# ST-Link-V2_1.net
KiCad netlist of a schematic drawn in Altium Designer
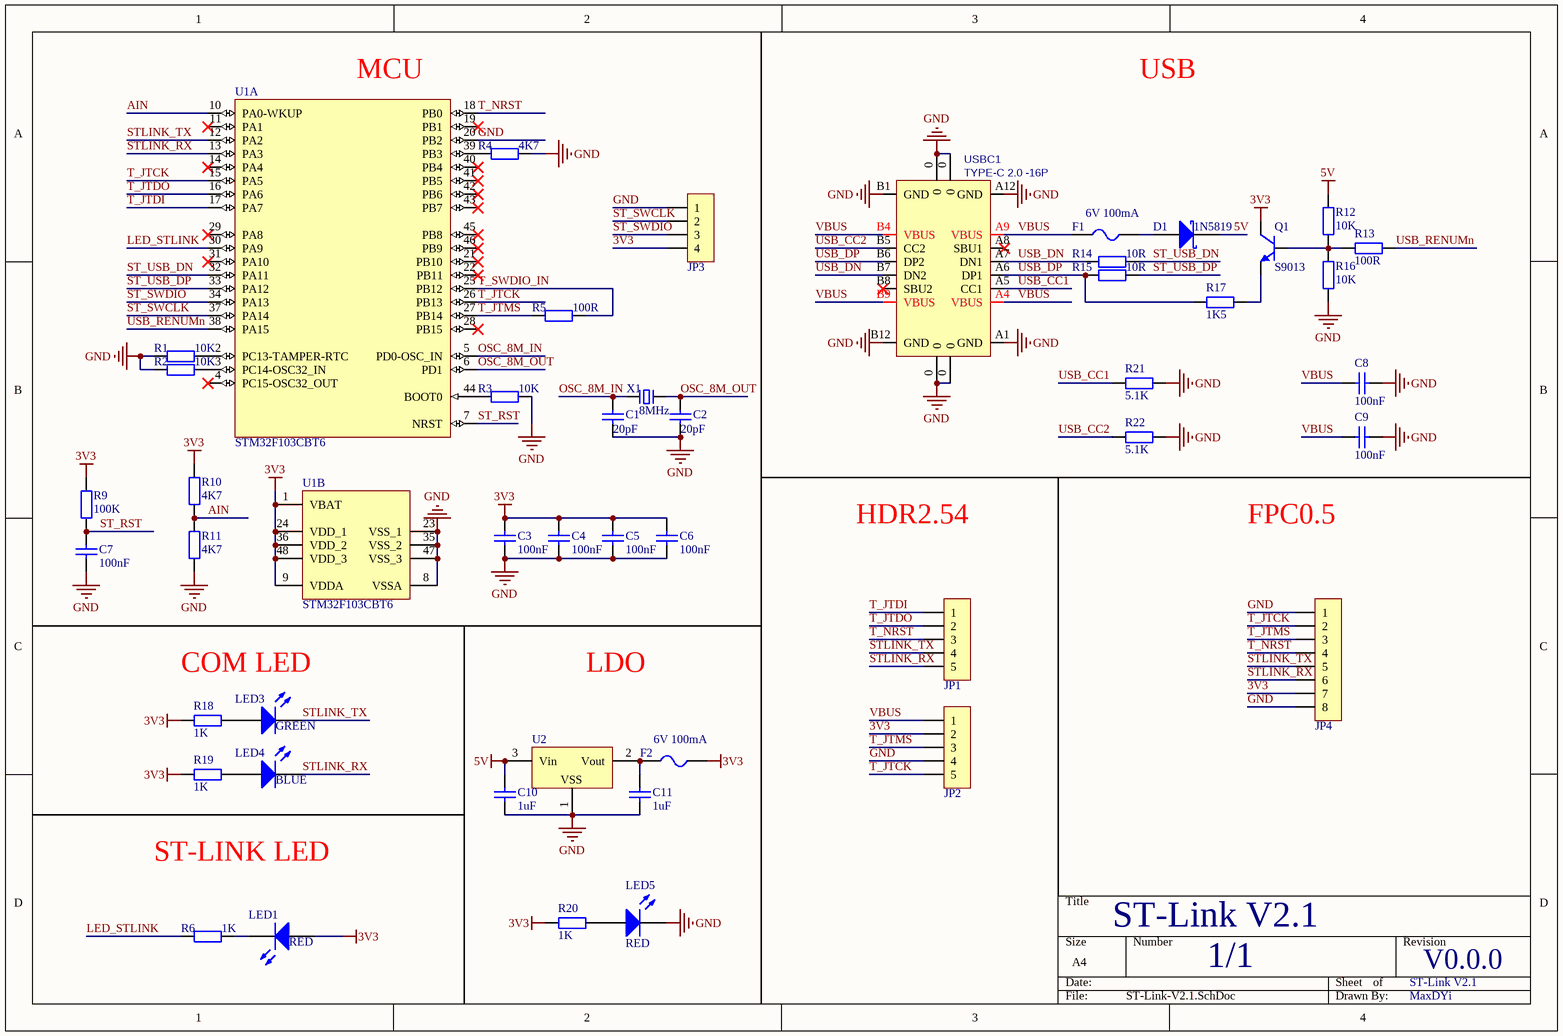
[diagram p0: ST-Link-V2.1.SchDoc]

(export (version "E")
  (design (tool "Eeschema 10.0.6"))
  (components
    (comp (ref "C1")
      (value "20pF")
      (footprint "C0402_M")
      (description "贴片电容/MLCC电容")
      (libsource (lib "0.1 - 电阻-电容-电感-保险丝-晶振-晶体-磁珠-电位器-法拉电容-馈通电容") (part "C"))
    )
    (comp (ref "C2")
      (value "20pF")
      (footprint "C0402_M")
      (description "贴片电容/MLCC电容")
      (libsource (lib "0.1 - 电阻-电容-电感-保险丝-晶振-晶体-磁珠-电位器-法拉电容-馈通电容") (part "C"))
    )
    (comp (ref "C3")
      (value "100nF")
      (footprint "C0402_M")
      (description "贴片电容/MLCC电容")
      (libsource (lib "0.1 - 电阻-电容-电感-保险丝-晶振-晶体-磁珠-电位器-法拉电容-馈通电容") (part "C"))
    )
    (comp (ref "C4")
      (value "100nF")
      (footprint "C0402_M")
      (description "贴片电容/MLCC电容")
      (libsource (lib "0.1 - 电阻-电容-电感-保险丝-晶振-晶体-磁珠-电位器-法拉电容-馈通电容") (part "C"))
    )
    (comp (ref "C5")
      (value "100nF")
      (footprint "C0402_M")
      (description "贴片电容/MLCC电容")
      (libsource (lib "0.1 - 电阻-电容-电感-保险丝-晶振-晶体-磁珠-电位器-法拉电容-馈通电容") (part "C"))
    )
    (comp (ref "C6")
      (value "100nF")
      (footprint "C0402_M")
      (description "贴片电容/MLCC电容")
      (libsource (lib "0.1 - 电阻-电容-电感-保险丝-晶振-晶体-磁珠-电位器-法拉电容-馈通电容") (part "C"))
    )
    (comp (ref "C7")
      (value "100nF")
      (footprint "C0402_M")
      (description "贴片电容/MLCC电容")
      (libsource (lib "0.1 - 电阻-电容-电感-保险丝-晶振-晶体-磁珠-电位器-法拉电容-馈通电容") (part "C"))
    )
    (comp (ref "C8")
      (value "100nF")
      (footprint "C0402_M")
      (description "贴片电容/MLCC电容")
      (libsource (lib "0.1 - 电阻-电容-电感-保险丝-晶振-晶体-磁珠-电位器-法拉电容-馈通电容") (part "C"))
    )
    (comp (ref "C9")
      (value "100nF")
      (footprint "C0402_M")
      (description "贴片电容/MLCC电容")
      (libsource (lib "0.1 - 电阻-电容-电感-保险丝-晶振-晶体-磁珠-电位器-法拉电容-馈通电容") (part "C"))
    )
    (comp (ref "C10")
      (value "1uF")
      (footprint "C0402_M")
      (description "贴片电容/MLCC电容")
      (libsource (lib "0.1 - 电阻-电容-电感-保险丝-晶振-晶体-磁珠-电位器-法拉电容-馈通电容") (part "C"))
    )
    (comp (ref "C11")
      (value "1uF")
      (footprint "C0402_M")
      (description "贴片电容/MLCC电容")
      (libsource (lib "0.1 - 电阻-电容-电感-保险丝-晶振-晶体-磁珠-电位器-法拉电容-馈通电容") (part "C"))
    )
    (comp (ref "D1")
      (value "1N5819")
      (footprint "SOD-323")
      (description "肖特基二极管")
      (libsource (lib "0.2 - 二极管-TVS-ESD-整流桥-放电管") (part "1N5819"))
    )
    (comp (ref "F1")
      (value "6V 100mA")
      (footprint "F0805")
      (description "方形保险丝")
      (libsource (lib "0.1 - 电阻-电容-电感-保险丝-晶振-晶体-磁珠-电位器-法拉电容-馈通电容") (part "FUSE-8.5*4.0*8.0"))
    )
    (comp (ref "F2")
      (value "6V 100mA")
      (footprint "F0805")
      (description "方形保险丝")
      (libsource (lib "0.1 - 电阻-电容-电感-保险丝-晶振-晶体-磁珠-电位器-法拉电容-馈通电容") (part "FUSE-8.5*4.0*8.0"))
    )
    (comp (ref "JP1")
      (value "HDR-1X5")
      (footprint "HDR2.54-WS-5P")
      (description "5P接插件")
      (libsource (lib "5.5 - 2.54mm连接器(KF2EDGK_XH2.54_2.54排针排母)") (part "Header 5"))
    )
    (comp (ref "JP2")
      (value "HDR-1X5")
      (footprint "HDR2.54-WS-5P")
      (description "5P接插件")
      (libsource (lib "5.5 - 2.54mm连接器(KF2EDGK_XH2.54_2.54排针排母)") (part "Header 5"))
    )
    (comp (ref "JP3")
      (value "HDR-1X4")
      (footprint "HDR1.27-LI-4P")
      (description "4P接插件")
      (libsource (lib "5.5 - 2.54mm连接器(KF2EDGK_XH2.54_2.54排针排母)") (part "Header 4"))
    )
    (comp (ref "JP4")
      (value "CON-8P")
      (footprint "FPC0.5-WT-8P-双侧触点")
      (description "8P连接器")
      (libsource (lib "4.9 - 0.5mm连接器(FPC0.5)") (part "Header 8"))
    )
    (comp (ref "LED1")
      (value "RED")
      (footprint "LED0603_R")
      (description "贴片LED")
      (libsource (lib "0.3 - LED发光二极管-IR二极管_接收管-光耦") (part "LED"))
    )
    (comp (ref "LED3")
      (value "GREEN")
      (footprint "LED0603_G")
      (description "贴片LED")
      (libsource (lib "0.3 - LED发光二极管-IR二极管_接收管-光耦") (part "LED"))
    )
    (comp (ref "LED4")
      (value "BLUE")
      (footprint "LED0603_B")
      (description "贴片LED")
      (libsource (lib "0.3 - LED发光二极管-IR二极管_接收管-光耦") (part "LED"))
    )
    (comp (ref "LED5")
      (value "RED")
      (footprint "LED0603_R")
      (description "贴片LED")
      (libsource (lib "0.3 - LED发光二极管-IR二极管_接收管-光耦") (part "LED"))
    )
    (comp (ref "Q1")
      (value "S9013")
      (footprint "SOT23-3N")
      (description "低频放大-NPN型")
      (libsource (lib "0.4 - 三极管-场效应管-可控硅") (part "9013-SMD"))
    )
    (comp (ref "R1")
      (value "10K")
      (footprint "R0402_M")
      (description "贴片电阻")
      (libsource (lib "0.1 - 电阻-电容-电感-保险丝-晶振-晶体-磁珠-电位器-法拉电容-馈通电容") (part "R"))
    )
    (comp (ref "R2")
      (value "10K")
      (footprint "R0402_M")
      (description "贴片电阻")
      (libsource (lib "0.1 - 电阻-电容-电感-保险丝-晶振-晶体-磁珠-电位器-法拉电容-馈通电容") (part "R"))
    )
    (comp (ref "R3")
      (value "10K")
      (footprint "R0402_M")
      (description "贴片电阻")
      (libsource (lib "0.1 - 电阻-电容-电感-保险丝-晶振-晶体-磁珠-电位器-法拉电容-馈通电容") (part "R"))
    )
    (comp (ref "R4")
      (value "4K7")
      (footprint "R0402_M")
      (description "贴片电阻")
      (libsource (lib "0.1 - 电阻-电容-电感-保险丝-晶振-晶体-磁珠-电位器-法拉电容-馈通电容") (part "R"))
    )
    (comp (ref "R5")
      (value "100R")
      (footprint "R0402_M")
      (description "贴片电阻")
      (libsource (lib "0.1 - 电阻-电容-电感-保险丝-晶振-晶体-磁珠-电位器-法拉电容-馈通电容") (part "R"))
    )
    (comp (ref "R6")
      (value "1K")
      (footprint "R0402_M")
      (description "贴片电阻")
      (libsource (lib "0.1 - 电阻-电容-电感-保险丝-晶振-晶体-磁珠-电位器-法拉电容-馈通电容") (part "R"))
    )
    (comp (ref "R9")
      (value "100K")
      (footprint "R0402_M")
      (description "贴片电阻")
      (libsource (lib "0.1 - 电阻-电容-电感-保险丝-晶振-晶体-磁珠-电位器-法拉电容-馈通电容") (part "R"))
    )
    (comp (ref "R10")
      (value "4K7")
      (footprint "R0402_M")
      (description "贴片电阻")
      (libsource (lib "0.1 - 电阻-电容-电感-保险丝-晶振-晶体-磁珠-电位器-法拉电容-馈通电容") (part "R"))
    )
    (comp (ref "R11")
      (value "4K7")
      (footprint "R0402_M")
      (description "贴片电阻")
      (libsource (lib "0.1 - 电阻-电容-电感-保险丝-晶振-晶体-磁珠-电位器-法拉电容-馈通电容") (part "R"))
    )
    (comp (ref "R12")
      (value "10K")
      (footprint "R0402_M")
      (description "贴片电阻")
      (libsource (lib "0.1 - 电阻-电容-电感-保险丝-晶振-晶体-磁珠-电位器-法拉电容-馈通电容") (part "R"))
    )
    (comp (ref "R13")
      (value "100R")
      (footprint "R0402_M")
      (description "贴片电阻")
      (libsource (lib "0.1 - 电阻-电容-电感-保险丝-晶振-晶体-磁珠-电位器-法拉电容-馈通电容") (part "R"))
    )
    (comp (ref "R14")
      (value "10R")
      (footprint "R0402_M")
      (description "贴片电阻")
      (libsource (lib "0.1 - 电阻-电容-电感-保险丝-晶振-晶体-磁珠-电位器-法拉电容-馈通电容") (part "R"))
    )
    (comp (ref "R15")
      (value "10R")
      (footprint "R0402_M")
      (description "贴片电阻")
      (libsource (lib "0.1 - 电阻-电容-电感-保险丝-晶振-晶体-磁珠-电位器-法拉电容-馈通电容") (part "R"))
    )
    (comp (ref "R16")
      (value "10K")
      (footprint "R0402_M")
      (description "贴片电阻")
      (libsource (lib "0.1 - 电阻-电容-电感-保险丝-晶振-晶体-磁珠-电位器-法拉电容-馈通电容") (part "R"))
    )
    (comp (ref "R17")
      (value "1K5")
      (footprint "R0402_M")
      (description "贴片电阻")
      (libsource (lib "0.1 - 电阻-电容-电感-保险丝-晶振-晶体-磁珠-电位器-法拉电容-馈通电容") (part "R"))
    )
    (comp (ref "R18")
      (value "1K")
      (footprint "R0402_M")
      (description "贴片电阻")
      (libsource (lib "0.1 - 电阻-电容-电感-保险丝-晶振-晶体-磁珠-电位器-法拉电容-馈通电容") (part "R"))
    )
    (comp (ref "R19")
      (value "1K")
      (footprint "R0402_M")
      (description "贴片电阻")
      (libsource (lib "0.1 - 电阻-电容-电感-保险丝-晶振-晶体-磁珠-电位器-法拉电容-馈通电容") (part "R"))
    )
    (comp (ref "R20")
      (value "1K")
      (footprint "R0402_M")
      (description "贴片电阻")
      (libsource (lib "0.1 - 电阻-电容-电感-保险丝-晶振-晶体-磁珠-电位器-法拉电容-馈通电容") (part "R"))
    )
    (comp (ref "R21")
      (value "5.1K")
      (footprint "R0402_M")
      (description "贴片电阻")
      (libsource (lib "0.1 - 电阻-电容-电感-保险丝-晶振-晶体-磁珠-电位器-法拉电容-馈通电容") (part "R"))
    )
    (comp (ref "R22")
      (value "5.1K")
      (footprint "R0402_M")
      (description "贴片电阻")
      (libsource (lib "0.1 - 电阻-电容-电感-保险丝-晶振-晶体-磁珠-电位器-法拉电容-馈通电容") (part "R"))
    )
    (comp (ref "U1")
      (value "STM32F103CBT6")
      (footprint "STM-LQFP48_N")
      (libsource (lib "2.4 - STM32 F1系列单片机") (part "STM32F103CBT6"))
    )
    (comp (ref "U2")
      (value "XC6206P332MR")
      (footprint "SOT23-3N")
      (description "LDO 3.3V/0.25A")
      (libsource (lib "0.7 - 电源类芯片") (part "XC6206P332MR"))
    )
    (comp (ref "USBC1")
      (value "TYPE-C 2.0 -16P")
      (footprint "USB-C-SMD_16P")
      (description "USB2.0_Type-C_16Pin母座")
      (libsource (lib "0.6 - 电源_音频_USB Type-C_HDMI_XT60_5557_D-SUB_RJ45_SD-TF_SIM插座") (part "USB2.0_Type-C_16Pin"))
    )
    (comp (ref "X1")
      (value "8MHz")
      (footprint "OSC-5032-2P")
      (description "2脚无源晶振(谐振器）")
      (libsource (lib "0.1 - 电阻-电容-电感-保险丝-晶振-晶体-磁珠-电位器-法拉电容-馈通电容") (part "XTAL-2P"))
    )
  )
  (nets
    (net (code "1") (name "/AIN") (class "Default")
      (node (ref "R10") (pin "1") (pinfunction "1_1") (pintype "passive"))
      (node (ref "R11") (pin "2") (pinfunction "2_2") (pintype "passive"))
      (node (ref "U1") (pin "10") (pinfunction "PA0-WKUP_10") (pintype "bidirectional"))
    )
    (net (code "2") (name "/LED_STLINK") (class "Default")
      (node (ref "R6") (pin "1") (pinfunction "1_1") (pintype "passive"))
      (node (ref "U1") (pin "30") (pinfunction "PA9_30") (pintype "bidirectional"))
    )
    (net (code "3") (name "/OSC_8M_IN") (class "Default")
      (node (ref "C1") (pin "2") (pinfunction "2_2") (pintype "passive"))
      (node (ref "U1") (pin "5") (pinfunction "PD0-OSC_IN_5") (pintype "bidirectional"))
      (node (ref "X1") (pin "1") (pinfunction "1_1") (pintype "passive"))
    )
    (net (code "4") (name "/OSC_8M_OUT") (class "Default")
      (node (ref "C2") (pin "2") (pinfunction "2_2") (pintype "passive"))
      (node (ref "U1") (pin "6") (pinfunction "PD1_6") (pintype "bidirectional"))
      (node (ref "X1") (pin "2") (pinfunction "2_2") (pintype "passive"))
    )
    (net (code "5") (name "/STLINK_RX") (class "Default")
      (node (ref "JP1") (pin "5") (pinfunction "5_5") (pintype "passive"))
      (node (ref "JP4") (pin "6") (pinfunction "6_6") (pintype "passive"))
      (node (ref "LED4") (pin "2") (pinfunction "K_2") (pintype "passive"))
      (node (ref "U1") (pin "13") (pinfunction "PA3_13") (pintype "bidirectional"))
    )
    (net (code "6") (name "/STLINK_TX") (class "Default")
      (node (ref "JP1") (pin "4") (pinfunction "4_4") (pintype "passive"))
      (node (ref "JP4") (pin "5") (pinfunction "5_5") (pintype "passive"))
      (node (ref "LED3") (pin "2") (pinfunction "K_2") (pintype "passive"))
      (node (ref "U1") (pin "12") (pinfunction "PA2_12") (pintype "bidirectional"))
    )
    (net (code "7") (name "/ST_RST") (class "Default")
      (node (ref "C7") (pin "2") (pinfunction "2_2") (pintype "passive"))
      (node (ref "R9") (pin "1") (pinfunction "1_1") (pintype "passive"))
      (node (ref "U1") (pin "7") (pinfunction "NRST_7") (pintype "bidirectional"))
    )
    (net (code "8") (name "/ST_SWCLK") (class "Default")
      (node (ref "JP3") (pin "2") (pinfunction "2_2") (pintype "passive"))
      (node (ref "U1") (pin "37") (pinfunction "PA14_37") (pintype "bidirectional"))
    )
    (net (code "9") (name "/ST_SWDIO") (class "Default")
      (node (ref "JP3") (pin "3") (pinfunction "3_3") (pintype "passive"))
      (node (ref "U1") (pin "34") (pinfunction "PA13_34") (pintype "bidirectional"))
    )
    (net (code "10") (name "/ST_USB_DN") (class "Default")
      (node (ref "R14") (pin "2") (pinfunction "2_2") (pintype "passive"))
      (node (ref "U1") (pin "32") (pinfunction "PA11_32") (pintype "bidirectional"))
    )
    (net (code "11") (name "/ST_USB_DP") (class "Default")
      (node (ref "R15") (pin "2") (pinfunction "2_2") (pintype "passive"))
      (node (ref "U1") (pin "33") (pinfunction "PA12_33") (pintype "bidirectional"))
    )
    (net (code "12") (name "/T_JTCK") (class "Default")
      (node (ref "JP2") (pin "5") (pinfunction "5_5") (pintype "passive"))
      (node (ref "JP4") (pin "2") (pinfunction "2_2") (pintype "passive"))
      (node (ref "U1") (pin "15") (pinfunction "PA5_15") (pintype "bidirectional"))
      (node (ref "U1") (pin "26") (pinfunction "PB13_26") (pintype "bidirectional"))
    )
    (net (code "13") (name "/T_JTDI") (class "Default")
      (node (ref "JP1") (pin "1") (pinfunction "1_1") (pintype "passive"))
      (node (ref "U1") (pin "17") (pinfunction "PA7_17") (pintype "bidirectional"))
    )
    (net (code "14") (name "/T_JTDO") (class "Default")
      (node (ref "JP1") (pin "2") (pinfunction "2_2") (pintype "passive"))
      (node (ref "U1") (pin "16") (pinfunction "PA6_16") (pintype "bidirectional"))
    )
    (net (code "15") (name "/T_JTMS") (class "Default")
      (node (ref "JP2") (pin "3") (pinfunction "3_3") (pintype "passive"))
      (node (ref "JP4") (pin "3") (pinfunction "3_3") (pintype "passive"))
      (node (ref "R5") (pin "1") (pinfunction "1_1") (pintype "passive"))
      (node (ref "U1") (pin "27") (pinfunction "PB14_27") (pintype "bidirectional"))
    )
    (net (code "16") (name "/T_NRST") (class "Default")
      (node (ref "JP1") (pin "3") (pinfunction "3_3") (pintype "passive"))
      (node (ref "JP4") (pin "4") (pinfunction "4_4") (pintype "passive"))
      (node (ref "U1") (pin "18") (pinfunction "PB0_18") (pintype "bidirectional"))
    )
    (net (code "17") (name "/T_SWDIO_IN") (class "Default")
      (node (ref "R5") (pin "2") (pinfunction "2_2") (pintype "passive"))
      (node (ref "U1") (pin "25") (pinfunction "PB12_25") (pintype "bidirectional"))
    )
    (net (code "18") (name "/USB_CC1") (class "Default")
      (node (ref "R21") (pin "2") (pinfunction "2_2") (pintype "passive"))
      (node (ref "USBC1") (pin "A5") (pinfunction "CC1_A5") (pintype "passive"))
    )
    (net (code "19") (name "/USB_CC2") (class "Default")
      (node (ref "R22") (pin "2") (pinfunction "2_2") (pintype "passive"))
      (node (ref "USBC1") (pin "B5") (pinfunction "CC2_B5") (pintype "passive"))
    )
    (net (code "20") (name "/USB_DN") (class "Default")
      (node (ref "R14") (pin "1") (pinfunction "1_1") (pintype "passive"))
      (node (ref "USBC1") (pin "A7") (pinfunction "DN1_A7") (pintype "passive"))
      (node (ref "USBC1") (pin "B7") (pinfunction "DN2_B7") (pintype "passive"))
    )
    (net (code "21") (name "/USB_DP") (class "Default")
      (node (ref "R15") (pin "1") (pinfunction "1_1") (pintype "passive"))
      (node (ref "R17") (pin "1") (pinfunction "1_1") (pintype "passive"))
      (node (ref "USBC1") (pin "A6") (pinfunction "DP1_A6") (pintype "passive"))
      (node (ref "USBC1") (pin "B6") (pinfunction "DP2_B6") (pintype "passive"))
    )
    (net (code "22") (name "/USB_RENUMn") (class "Default")
      (node (ref "R13") (pin "1") (pinfunction "1_1") (pintype "passive"))
      (node (ref "U1") (pin "38") (pinfunction "PA15_38") (pintype "bidirectional"))
    )
    (net (code "23") (name "/VBUS") (class "Default")
      (node (ref "C8") (pin "1") (pinfunction "1_1") (pintype "passive"))
      (node (ref "C9") (pin "1") (pinfunction "1_1") (pintype "passive"))
      (node (ref "F1") (pin "2") (pinfunction "2_2") (pintype "passive"))
      (node (ref "JP2") (pin "1") (pinfunction "1_1") (pintype "passive"))
      (node (ref "USBC1") (pin "A4") (pinfunction "VBUS_A4") (pintype "passive"))
      (node (ref "USBC1") (pin "A9") (pinfunction "VBUS_A9") (pintype "passive"))
      (node (ref "USBC1") (pin "B4") (pinfunction "VBUS_B4") (pintype "passive"))
      (node (ref "USBC1") (pin "B9") (pinfunction "VBUS_B9") (pintype "passive"))
    )
    (net (code "24") (name "3V3") (class "Default")
      (node (ref "C3") (pin "2") (pinfunction "2_2") (pintype "passive"))
      (node (ref "C4") (pin "2") (pinfunction "2_2") (pintype "passive"))
      (node (ref "C5") (pin "2") (pinfunction "2_2") (pintype "passive"))
      (node (ref "C6") (pin "2") (pinfunction "2_2") (pintype "passive"))
      (node (ref "F2") (pin "1") (pinfunction "1_1") (pintype "passive"))
      (node (ref "JP2") (pin "2") (pinfunction "2_2") (pintype "passive"))
      (node (ref "JP3") (pin "4") (pinfunction "4_4") (pintype "passive"))
      (node (ref "JP4") (pin "7") (pinfunction "7_7") (pintype "passive"))
      (node (ref "LED1") (pin "1") (pinfunction "A_1") (pintype "passive"))
      (node (ref "Q1") (pin "3") (pinfunction "C_3") (pintype "passive"))
      (node (ref "R10") (pin "2") (pinfunction "2_2") (pintype "passive"))
      (node (ref "R18") (pin "2") (pinfunction "2_2") (pintype "passive"))
      (node (ref "R19") (pin "2") (pinfunction "2_2") (pintype "passive"))
      (node (ref "R20") (pin "2") (pinfunction "2_2") (pintype "passive"))
      (node (ref "R9") (pin "2") (pinfunction "2_2") (pintype "passive"))
      (node (ref "U1") (pin "1") (pinfunction "VBAT_1") (pintype "power_in"))
      (node (ref "U1") (pin "24") (pinfunction "VDD_1_24") (pintype "power_in"))
      (node (ref "U1") (pin "36") (pinfunction "VDD_2_36") (pintype "power_in"))
      (node (ref "U1") (pin "48") (pinfunction "VDD_3_48") (pintype "power_in"))
      (node (ref "U1") (pin "9") (pinfunction "VDDA_9") (pintype "power_in"))
    )
    (net (code "25") (name "5V") (class "Default")
      (node (ref "C10") (pin "2") (pinfunction "2_2") (pintype "passive"))
      (node (ref "D1") (pin "2") (pinfunction "K_2") (pintype "passive"))
      (node (ref "R12") (pin "2") (pinfunction "2_2") (pintype "passive"))
      (node (ref "U2") (pin "3") (pinfunction "Vin_3") (pintype "passive"))
    )
    (net (code "26") (name "GND") (class "Default")
      (node (ref "C1") (pin "1") (pinfunction "1_1") (pintype "passive"))
      (node (ref "C10") (pin "1") (pinfunction "1_1") (pintype "passive"))
      (node (ref "C11") (pin "1") (pinfunction "1_1") (pintype "passive"))
      (node (ref "C2") (pin "1") (pinfunction "1_1") (pintype "passive"))
      (node (ref "C3") (pin "1") (pinfunction "1_1") (pintype "passive"))
      (node (ref "C4") (pin "1") (pinfunction "1_1") (pintype "passive"))
      (node (ref "C5") (pin "1") (pinfunction "1_1") (pintype "passive"))
      (node (ref "C6") (pin "1") (pinfunction "1_1") (pintype "passive"))
      (node (ref "C7") (pin "1") (pinfunction "1_1") (pintype "passive"))
      (node (ref "C8") (pin "2") (pinfunction "2_2") (pintype "passive"))
      (node (ref "C9") (pin "2") (pinfunction "2_2") (pintype "passive"))
      (node (ref "JP2") (pin "4") (pinfunction "4_4") (pintype "passive"))
      (node (ref "JP3") (pin "1") (pinfunction "1_1") (pintype "passive"))
      (node (ref "JP4") (pin "1") (pinfunction "1_1") (pintype "passive"))
      (node (ref "JP4") (pin "8") (pinfunction "8_8") (pintype "passive"))
      (node (ref "LED5") (pin "2") (pinfunction "K_2") (pintype "passive"))
      (node (ref "R1") (pin "1") (pinfunction "1_1") (pintype "passive"))
      (node (ref "R11") (pin "1") (pinfunction "1_1") (pintype "passive"))
      (node (ref "R16") (pin "1") (pinfunction "1_1") (pintype "passive"))
      (node (ref "R2") (pin "1") (pinfunction "1_1") (pintype "passive"))
      (node (ref "R21") (pin "1") (pinfunction "1_1") (pintype "passive"))
      (node (ref "R22") (pin "1") (pinfunction "1_1") (pintype "passive"))
      (node (ref "R3") (pin "2") (pinfunction "2_2") (pintype "passive"))
      (node (ref "R4") (pin "2") (pinfunction "2_2") (pintype "passive"))
      (node (ref "U1") (pin "20") (pinfunction "PB2_20") (pintype "bidirectional"))
      (node (ref "U1") (pin "23") (pinfunction "VSS_1_23") (pintype "power_in"))
      (node (ref "U1") (pin "35") (pinfunction "VSS_2_35") (pintype "power_in"))
      (node (ref "U1") (pin "47") (pinfunction "VSS_3_47") (pintype "power_in"))
      (node (ref "U1") (pin "8") (pinfunction "VSSA_8") (pintype "power_in"))
      (node (ref "U2") (pin "1") (pinfunction "GND_1") (pintype "passive"))
      (node (ref "USBC1") (pin "0") (pinfunction "0_0") (pintype "passive"))
      (node (ref "USBC1") (pin "A1") (pinfunction "GND_A1") (pintype "passive"))
      (node (ref "USBC1") (pin "A12") (pinfunction "GND_A12") (pintype "passive"))
      (node (ref "USBC1") (pin "B1") (pinfunction "GND_B1") (pintype "passive"))
      (node (ref "USBC1") (pin "B12") (pinfunction "GND_B12") (pintype "passive"))
    )
    (net (code "27") (name "Net-(D1-A)") (class "Default")
      (node (ref "D1") (pin "1") (pinfunction "A_1") (pintype "passive"))
      (node (ref "F1") (pin "1") (pinfunction "1_1") (pintype "passive"))
    )
    (net (code "28") (name "Net-(LED1-K)") (class "Default")
      (node (ref "LED1") (pin "2") (pinfunction "K_2") (pintype "passive"))
      (node (ref "R6") (pin "2") (pinfunction "2_2") (pintype "passive"))
    )
    (net (code "29") (name "Net-(LED3-A)") (class "Default")
      (node (ref "LED3") (pin "1") (pinfunction "A_1") (pintype "passive"))
      (node (ref "R18") (pin "1") (pinfunction "1_1") (pintype "passive"))
    )
    (net (code "30") (name "Net-(LED4-A)") (class "Default")
      (node (ref "LED4") (pin "1") (pinfunction "A_1") (pintype "passive"))
      (node (ref "R19") (pin "1") (pinfunction "1_1") (pintype "passive"))
    )
    (net (code "31") (name "Net-(LED5-A)") (class "Default")
      (node (ref "LED5") (pin "1") (pinfunction "A_1") (pintype "passive"))
      (node (ref "R20") (pin "1") (pinfunction "1_1") (pintype "passive"))
    )
    (net (code "32") (name "Net-(Q1-B)") (class "Default")
      (node (ref "Q1") (pin "1") (pinfunction "B_1") (pintype "passive"))
      (node (ref "R12") (pin "1") (pinfunction "1_1") (pintype "passive"))
      (node (ref "R13") (pin "2") (pinfunction "2_2") (pintype "passive"))
      (node (ref "R16") (pin "2") (pinfunction "2_2") (pintype "passive"))
    )
    (net (code "33") (name "Net-(Q1-E)") (class "Default")
      (node (ref "Q1") (pin "2") (pinfunction "E_2") (pintype "passive"))
      (node (ref "R17") (pin "2") (pinfunction "2_2") (pintype "passive"))
    )
    (net (code "34") (name "Net-(U1A-BOOT0)") (class "Default")
      (node (ref "R3") (pin "1") (pinfunction "1_1") (pintype "passive"))
      (node (ref "U1") (pin "44") (pinfunction "BOOT0_44") (pintype "input"))
    )
    (net (code "35") (name "Net-(U1A-PB3)") (class "Default")
      (node (ref "R4") (pin "1") (pinfunction "1_1") (pintype "passive"))
      (node (ref "U1") (pin "39") (pinfunction "PB3_39") (pintype "bidirectional"))
    )
    (net (code "36") (name "Net-(U1A-PC13-TAMPER-RTC)") (class "Default")
      (node (ref "R1") (pin "2") (pinfunction "2_2") (pintype "passive"))
      (node (ref "U1") (pin "2") (pinfunction "PC13-TAMPER-RTC_2") (pintype "bidirectional"))
    )
    (net (code "37") (name "Net-(U1A-PC14-OSC32_IN)") (class "Default")
      (node (ref "R2") (pin "2") (pinfunction "2_2") (pintype "passive"))
      (node (ref "U1") (pin "3") (pinfunction "PC14-OSC32_IN_3") (pintype "bidirectional"))
    )
    (net (code "38") (name "Net-(U2-Vout)") (class "Default")
      (node (ref "C11") (pin "2") (pinfunction "2_2") (pintype "passive"))
      (node (ref "F2") (pin "2") (pinfunction "2_2") (pintype "passive"))
      (node (ref "U2") (pin "2") (pinfunction "Vout_2") (pintype "passive"))
    )
    (net (code "39") (name "unconnected-(U1A-PA1-Pad11)") (class "Default")
      (node (ref "U1") (pin "11") (pinfunction "PA1_11") (pintype "bidirectional+no_connect"))
    )
    (net (code "40") (name "unconnected-(U1A-PA4-Pad14)") (class "Default")
      (node (ref "U1") (pin "14") (pinfunction "PA4_14") (pintype "bidirectional+no_connect"))
    )
    (net (code "41") (name "unconnected-(U1A-PA8-Pad29)") (class "Default")
      (node (ref "U1") (pin "29") (pinfunction "PA8_29") (pintype "bidirectional+no_connect"))
    )
    (net (code "42") (name "unconnected-(U1A-PA10-Pad31)") (class "Default")
      (node (ref "U1") (pin "31") (pinfunction "PA10_31") (pintype "bidirectional+no_connect"))
    )
    (net (code "43") (name "unconnected-(U1A-PB1-Pad19)") (class "Default")
      (node (ref "U1") (pin "19") (pinfunction "PB1_19") (pintype "bidirectional+no_connect"))
    )
    (net (code "44") (name "unconnected-(U1A-PB4-Pad40)") (class "Default")
      (node (ref "U1") (pin "40") (pinfunction "PB4_40") (pintype "bidirectional+no_connect"))
    )
    (net (code "45") (name "unconnected-(U1A-PB5-Pad41)") (class "Default")
      (node (ref "U1") (pin "41") (pinfunction "PB5_41") (pintype "bidirectional+no_connect"))
    )
    (net (code "46") (name "unconnected-(U1A-PB6-Pad42)") (class "Default")
      (node (ref "U1") (pin "42") (pinfunction "PB6_42") (pintype "bidirectional+no_connect"))
    )
    (net (code "47") (name "unconnected-(U1A-PB7-Pad43)") (class "Default")
      (node (ref "U1") (pin "43") (pinfunction "PB7_43") (pintype "bidirectional+no_connect"))
    )
    (net (code "48") (name "unconnected-(U1A-PB8-Pad45)") (class "Default")
      (node (ref "U1") (pin "45") (pinfunction "PB8_45") (pintype "bidirectional+no_connect"))
    )
    (net (code "49") (name "unconnected-(U1A-PB9-Pad46)") (class "Default")
      (node (ref "U1") (pin "46") (pinfunction "PB9_46") (pintype "bidirectional+no_connect"))
    )
    (net (code "50") (name "unconnected-(U1A-PB10-Pad21)") (class "Default")
      (node (ref "U1") (pin "21") (pinfunction "PB10_21") (pintype "bidirectional+no_connect"))
    )
    (net (code "51") (name "unconnected-(U1A-PB11-Pad22)") (class "Default")
      (node (ref "U1") (pin "22") (pinfunction "PB11_22") (pintype "bidirectional+no_connect"))
    )
    (net (code "52") (name "unconnected-(U1A-PB15-Pad28)") (class "Default")
      (node (ref "U1") (pin "28") (pinfunction "PB15_28") (pintype "bidirectional+no_connect"))
    )
    (net (code "53") (name "unconnected-(U1A-PC15-OSC32_OUT-Pad4)") (class "Default")
      (node (ref "U1") (pin "4") (pinfunction "PC15-OSC32_OUT_4") (pintype "bidirectional+no_connect"))
    )
    (net (code "54") (name "unconnected-(USBC1-SBU1-PadA8)") (class "Default")
      (node (ref "USBC1") (pin "A8") (pinfunction "SBU1_A8") (pintype "passive+no_connect"))
    )
    (net (code "55") (name "unconnected-(USBC1-SBU2-PadB8)") (class "Default")
      (node (ref "USBC1") (pin "B8") (pinfunction "SBU2_B8") (pintype "passive+no_connect"))
    )
  )
)
